# piZero_node.net
KiCad netlist of a schematic drawn in EAGLE
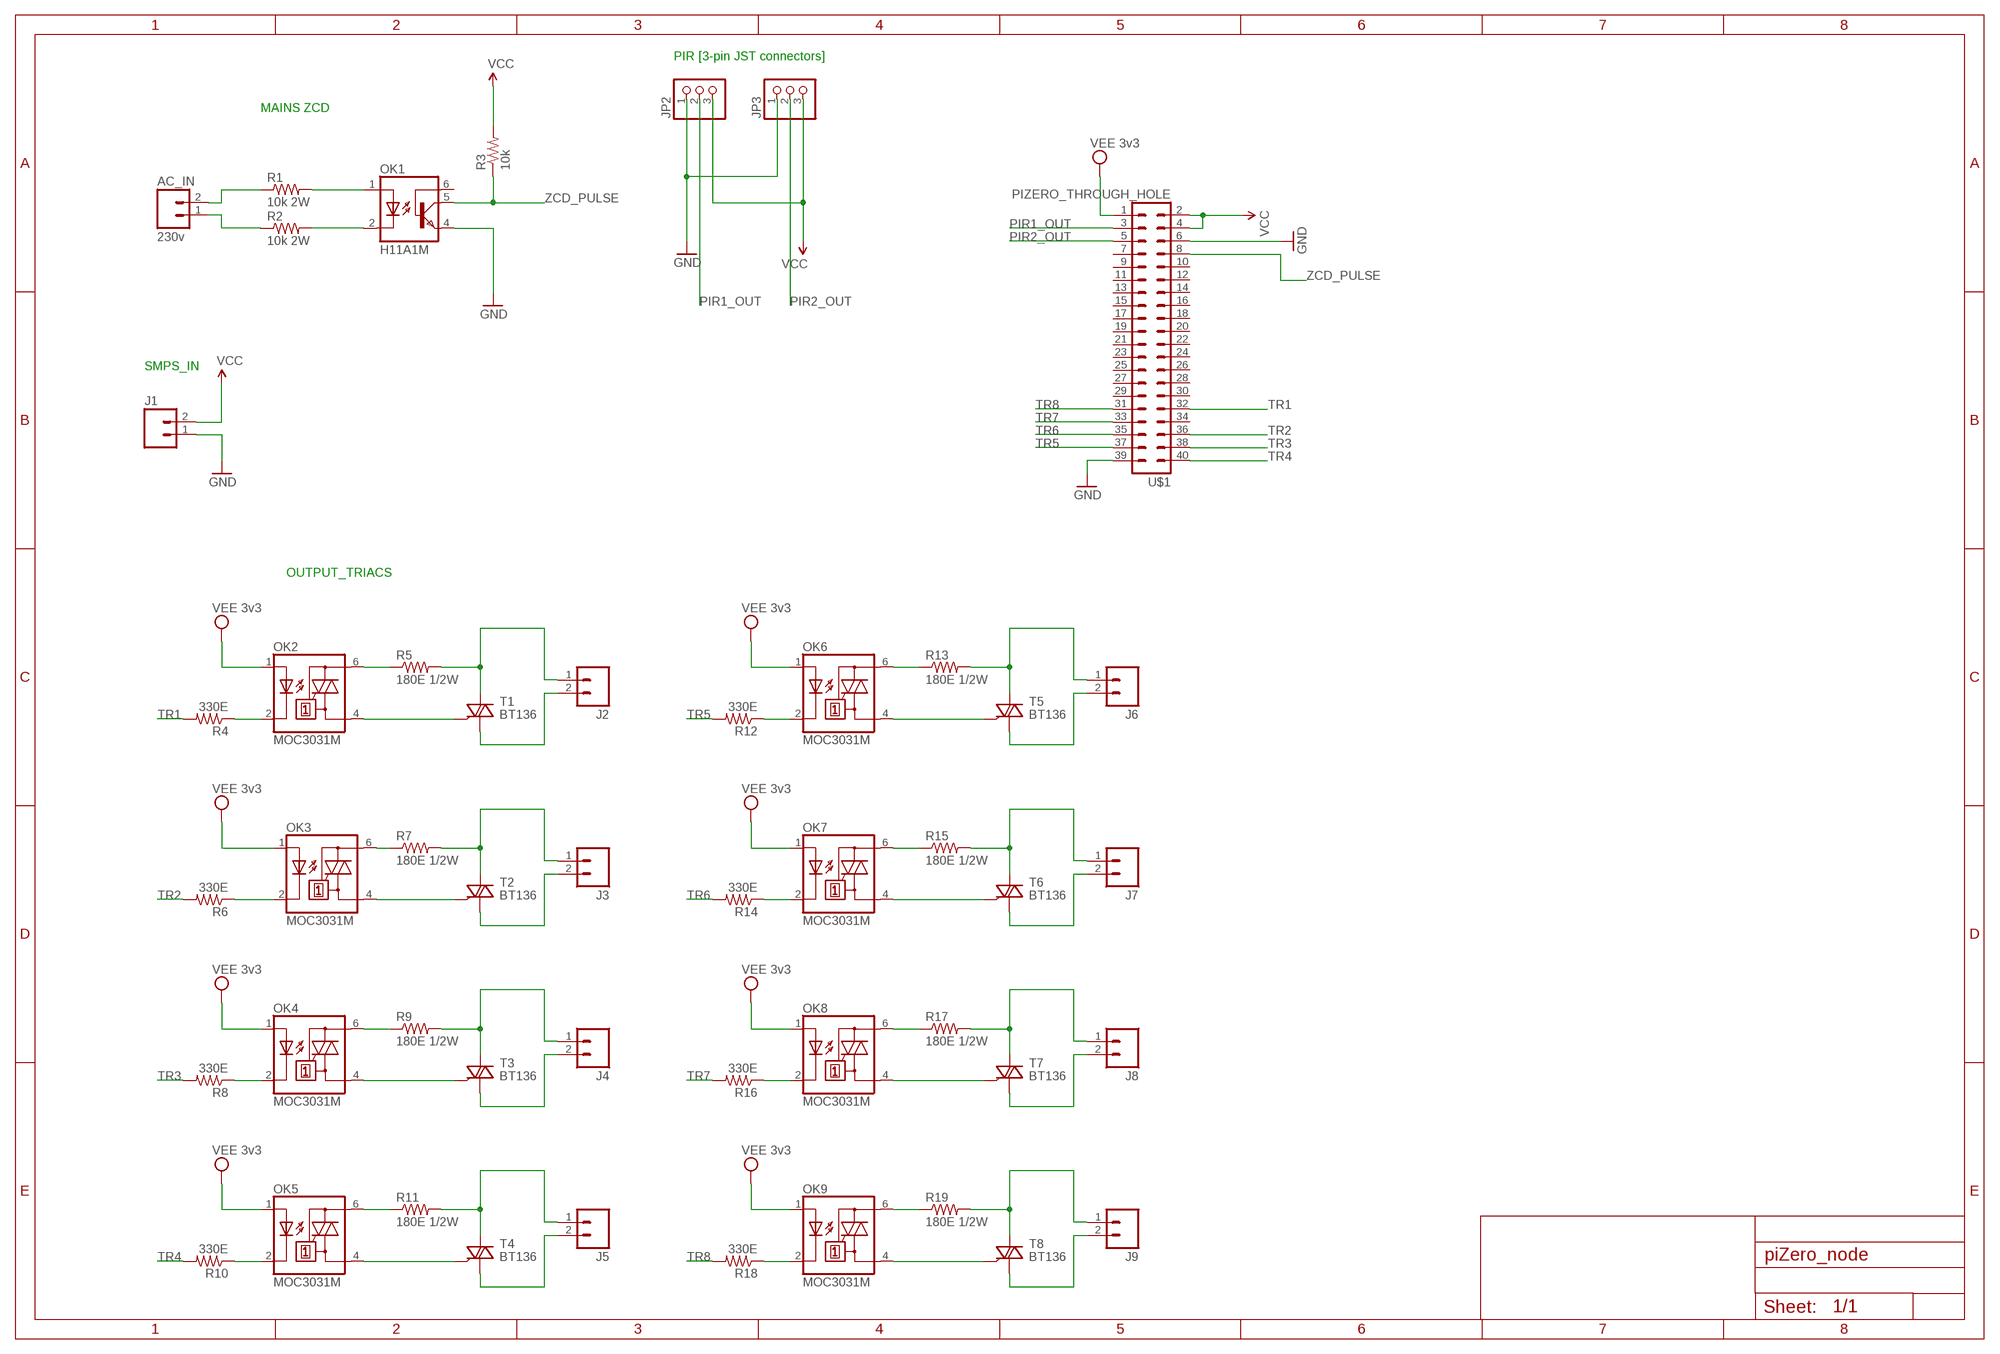
[diagram p0: schematic, sheet 1]

(export (version "E")
  (design (tool "Eeschema 10.0.6"))
  (components
    (comp (ref "AC_IN")
      (value "230v")
      (footprint "eagle-import:SCREWTERMINAL-3.5MM-2_LOCK")
      (libsource (lib "eagle-import") (part "M023.5MM_LOCK"))
    )
    (comp (ref "J1")
      (value "M023.5MM_LOCK")
      (footprint "eagle-import:SCREWTERMINAL-3.5MM-2_LOCK")
      (libsource (lib "eagle-import") (part "M023.5MM_LOCK"))
    )
    (comp (ref "J2")
      (value "M023.5MM_LOCK")
      (footprint "eagle-import:SCREWTERMINAL-3.5MM-2_LOCK")
      (libsource (lib "eagle-import") (part "M023.5MM_LOCK"))
    )
    (comp (ref "J3")
      (value "M023.5MM_LOCK")
      (footprint "eagle-import:SCREWTERMINAL-3.5MM-2_LOCK")
      (libsource (lib "eagle-import") (part "M023.5MM_LOCK"))
    )
    (comp (ref "J4")
      (value "M023.5MM_LOCK")
      (footprint "eagle-import:SCREWTERMINAL-3.5MM-2_LOCK")
      (libsource (lib "eagle-import") (part "M023.5MM_LOCK"))
    )
    (comp (ref "J5")
      (value "M023.5MM_LOCK")
      (footprint "eagle-import:SCREWTERMINAL-3.5MM-2_LOCK")
      (libsource (lib "eagle-import") (part "M023.5MM_LOCK"))
    )
    (comp (ref "J6")
      (value "M023.5MM_LOCK")
      (footprint "eagle-import:SCREWTERMINAL-3.5MM-2_LOCK")
      (libsource (lib "eagle-import") (part "M023.5MM_LOCK"))
    )
    (comp (ref "J7")
      (value "M023.5MM_LOCK")
      (footprint "eagle-import:SCREWTERMINAL-3.5MM-2_LOCK")
      (libsource (lib "eagle-import") (part "M023.5MM_LOCK"))
    )
    (comp (ref "J8")
      (value "M023.5MM_LOCK")
      (footprint "eagle-import:SCREWTERMINAL-3.5MM-2_LOCK")
      (libsource (lib "eagle-import") (part "M023.5MM_LOCK"))
    )
    (comp (ref "J9")
      (value "M023.5MM_LOCK")
      (footprint "eagle-import:SCREWTERMINAL-3.5MM-2_LOCK")
      (libsource (lib "eagle-import") (part "M023.5MM_LOCK"))
    )
    (comp (ref "JP2")
      (value "PINHD-1X3")
      (footprint "eagle-import:1X03")
      (libsource (lib "eagle-import") (part "PINHD-1X3"))
    )
    (comp (ref "JP3")
      (value "PINHD-1X3")
      (footprint "eagle-import:1X03")
      (libsource (lib "eagle-import") (part "PINHD-1X3"))
    )
    (comp (ref "OK1")
      (value "H11A1M")
      (footprint "eagle-import:DIL06")
      (fields (field (name "MPN") "H11A1-M"))
      (libsource (lib "eagle-import") (part "H11A?M1"))
    )
    (comp (ref "OK2")
      (value "MOC3031M")
      (footprint "eagle-import:DIL06")
      (fields (field (name "MF") "FAIRCHILD SEMICONDUCTOR"))
      (libsource (lib "eagle-import") (part "MOC3031M"))
    )
    (comp (ref "OK3")
      (value "MOC3031M")
      (footprint "eagle-import:DIL06")
      (fields (field (name "MF") "FAIRCHILD SEMICONDUCTOR"))
      (libsource (lib "eagle-import") (part "MOC3031M"))
    )
    (comp (ref "OK4")
      (value "MOC3031M")
      (footprint "eagle-import:DIL06")
      (fields (field (name "MF") "FAIRCHILD SEMICONDUCTOR"))
      (libsource (lib "eagle-import") (part "MOC3031M"))
    )
    (comp (ref "OK5")
      (value "MOC3031M")
      (footprint "eagle-import:DIL06")
      (fields (field (name "MF") "FAIRCHILD SEMICONDUCTOR"))
      (libsource (lib "eagle-import") (part "MOC3031M"))
    )
    (comp (ref "OK6")
      (value "MOC3031M")
      (footprint "eagle-import:DIL06")
      (fields (field (name "MF") "FAIRCHILD SEMICONDUCTOR"))
      (libsource (lib "eagle-import") (part "MOC3031M"))
    )
    (comp (ref "OK7")
      (value "MOC3031M")
      (footprint "eagle-import:DIL06")
      (fields (field (name "MF") "FAIRCHILD SEMICONDUCTOR"))
      (libsource (lib "eagle-import") (part "MOC3031M"))
    )
    (comp (ref "OK8")
      (value "MOC3031M")
      (footprint "eagle-import:DIL06")
      (fields (field (name "MF") "FAIRCHILD SEMICONDUCTOR"))
      (libsource (lib "eagle-import") (part "MOC3031M"))
    )
    (comp (ref "OK9")
      (value "MOC3031M")
      (footprint "eagle-import:DIL06")
      (fields (field (name "MF") "FAIRCHILD SEMICONDUCTOR"))
      (libsource (lib "eagle-import") (part "MOC3031M"))
    )
    (comp (ref "R1")
      (value "10k 2W")
      (footprint "eagle-import:AXIAL-0.8")
      (libsource (lib "eagle-import") (part "RESISTORPTH-2W"))
    )
    (comp (ref "R2")
      (value "10k 2W")
      (footprint "eagle-import:AXIAL-0.8")
      (libsource (lib "eagle-import") (part "RESISTORPTH-2W"))
    )
    (comp (ref "R3")
      (value "10k")
      (footprint "eagle-import:AXIAL-0.4")
      (libsource (lib "eagle-import") (part "RESISTORPTH-1/4W"))
    )
    (comp (ref "R4")
      (value "330E")
      (footprint "eagle-import:AXIAL-0.4")
      (libsource (lib "eagle-import") (part "RESISTORPTH-1/4W"))
    )
    (comp (ref "R5")
      (value "180E 1/2W")
      (footprint "eagle-import:AXIAL-0.5")
      (libsource (lib "eagle-import") (part "RESISTORPTH-1/2W"))
    )
    (comp (ref "R6")
      (value "330E")
      (footprint "eagle-import:AXIAL-0.4")
      (libsource (lib "eagle-import") (part "RESISTORPTH-1/4W"))
    )
    (comp (ref "R7")
      (value "180E 1/2W")
      (footprint "eagle-import:AXIAL-0.5")
      (libsource (lib "eagle-import") (part "RESISTORPTH-1/2W"))
    )
    (comp (ref "R8")
      (value "330E")
      (footprint "eagle-import:AXIAL-0.4")
      (libsource (lib "eagle-import") (part "RESISTORPTH-1/4W"))
    )
    (comp (ref "R9")
      (value "180E 1/2W")
      (footprint "eagle-import:AXIAL-0.5")
      (libsource (lib "eagle-import") (part "RESISTORPTH-1/2W"))
    )
    (comp (ref "R10")
      (value "330E")
      (footprint "eagle-import:AXIAL-0.4")
      (libsource (lib "eagle-import") (part "RESISTORPTH-1/4W"))
    )
    (comp (ref "R11")
      (value "180E 1/2W")
      (footprint "eagle-import:AXIAL-0.5")
      (libsource (lib "eagle-import") (part "RESISTORPTH-1/2W"))
    )
    (comp (ref "R12")
      (value "330E")
      (footprint "eagle-import:AXIAL-0.4")
      (libsource (lib "eagle-import") (part "RESISTORPTH-1/4W"))
    )
    (comp (ref "R13")
      (value "180E 1/2W")
      (footprint "eagle-import:AXIAL-0.5")
      (libsource (lib "eagle-import") (part "RESISTORPTH-1/2W"))
    )
    (comp (ref "R14")
      (value "330E")
      (footprint "eagle-import:AXIAL-0.4")
      (libsource (lib "eagle-import") (part "RESISTORPTH-1/4W"))
    )
    (comp (ref "R15")
      (value "180E 1/2W")
      (footprint "eagle-import:AXIAL-0.5")
      (libsource (lib "eagle-import") (part "RESISTORPTH-1/2W"))
    )
    (comp (ref "R16")
      (value "330E")
      (footprint "eagle-import:AXIAL-0.4")
      (libsource (lib "eagle-import") (part "RESISTORPTH-1/4W"))
    )
    (comp (ref "R17")
      (value "180E 1/2W")
      (footprint "eagle-import:AXIAL-0.5")
      (libsource (lib "eagle-import") (part "RESISTORPTH-1/2W"))
    )
    (comp (ref "R18")
      (value "330E")
      (footprint "eagle-import:AXIAL-0.4")
      (libsource (lib "eagle-import") (part "RESISTORPTH-1/4W"))
    )
    (comp (ref "R19")
      (value "180E 1/2W")
      (footprint "eagle-import:AXIAL-0.5")
      (libsource (lib "eagle-import") (part "RESISTORPTH-1/2W"))
    )
    (comp (ref "T1")
      (value "BT136")
      (footprint "eagle-import:TO220AB")
      (libsource (lib "eagle-import") (part "BT136"))
    )
    (comp (ref "T2")
      (value "BT136")
      (footprint "eagle-import:TO220AB")
      (libsource (lib "eagle-import") (part "BT136"))
    )
    (comp (ref "T3")
      (value "BT136")
      (footprint "eagle-import:TO220AB")
      (libsource (lib "eagle-import") (part "BT136"))
    )
    (comp (ref "T4")
      (value "BT136")
      (footprint "eagle-import:TO220AB")
      (libsource (lib "eagle-import") (part "BT136"))
    )
    (comp (ref "T5")
      (value "BT136")
      (footprint "eagle-import:TO220AB")
      (libsource (lib "eagle-import") (part "BT136"))
    )
    (comp (ref "T6")
      (value "BT136")
      (footprint "eagle-import:TO220AB")
      (libsource (lib "eagle-import") (part "BT136"))
    )
    (comp (ref "T7")
      (value "BT136")
      (footprint "eagle-import:TO220AB")
      (libsource (lib "eagle-import") (part "BT136"))
    )
    (comp (ref "T8")
      (value "BT136")
      (footprint "eagle-import:TO220AB")
      (libsource (lib "eagle-import") (part "BT136"))
    )
    (comp (ref "U$1")
      (value "PIZERO_THROUGH_HOLE")
      (footprint "eagle-import:PIZERO_THOUGH_HOLE")
      (libsource (lib "eagle-import") (part "PIZERO_THROUGH_HOLE"))
    )
  )
  (nets
    (net (code "1") (name "/PIR1_OUT") (class "Default")
      (node (ref "JP2") (pin "2") (pinfunction "2_2") (pintype "passive"))
      (node (ref "U$1") (pin "3") (pinfunction "3_3") (pintype "passive"))
    )
    (net (code "2") (name "/PIR2_OUT") (class "Default")
      (node (ref "JP3") (pin "2") (pinfunction "2_2") (pintype "passive"))
      (node (ref "U$1") (pin "5") (pinfunction "5_5") (pintype "passive"))
    )
    (net (code "3") (name "/TR1") (class "Default")
      (node (ref "R4") (pin "P$2") (pinfunction "2_P$2") (pintype "passive"))
      (node (ref "U$1") (pin "32") (pinfunction "32_32") (pintype "passive"))
    )
    (net (code "4") (name "/TR2") (class "Default")
      (node (ref "R6") (pin "P$2") (pinfunction "2_P$2") (pintype "passive"))
      (node (ref "U$1") (pin "36") (pinfunction "36_36") (pintype "passive"))
    )
    (net (code "5") (name "/TR3") (class "Default")
      (node (ref "R8") (pin "P$2") (pinfunction "2_P$2") (pintype "passive"))
      (node (ref "U$1") (pin "38") (pinfunction "38_38") (pintype "passive"))
    )
    (net (code "6") (name "/TR4") (class "Default")
      (node (ref "R10") (pin "P$2") (pinfunction "2_P$2") (pintype "passive"))
      (node (ref "U$1") (pin "40") (pinfunction "40_40") (pintype "passive"))
    )
    (net (code "7") (name "/TR5") (class "Default")
      (node (ref "R12") (pin "P$2") (pinfunction "2_P$2") (pintype "passive"))
      (node (ref "U$1") (pin "37") (pinfunction "37_37") (pintype "passive"))
    )
    (net (code "8") (name "/TR6") (class "Default")
      (node (ref "R14") (pin "P$2") (pinfunction "2_P$2") (pintype "passive"))
      (node (ref "U$1") (pin "35") (pinfunction "35_35") (pintype "passive"))
    )
    (net (code "9") (name "/TR7") (class "Default")
      (node (ref "R16") (pin "P$2") (pinfunction "2_P$2") (pintype "passive"))
      (node (ref "U$1") (pin "33") (pinfunction "33_33") (pintype "passive"))
    )
    (net (code "10") (name "/TR8") (class "Default")
      (node (ref "R18") (pin "P$2") (pinfunction "2_P$2") (pintype "passive"))
      (node (ref "U$1") (pin "31") (pinfunction "31_31") (pintype "passive"))
    )
    (net (code "11") (name "/ZCD_PULSE") (class "Default")
      (node (ref "OK1") (pin "5") (pinfunction "COL_5") (pintype "passive"))
      (node (ref "R3") (pin "P$1") (pinfunction "1_P$1") (pintype "passive"))
      (node (ref "U$1") (pin "8") (pinfunction "8_8") (pintype "passive"))
    )
    (net (code "12") (name "GND") (class "Default")
      (node (ref "J1") (pin "1") (pinfunction "1_1") (pintype "passive"))
      (node (ref "JP2") (pin "1") (pinfunction "1_1") (pintype "passive"))
      (node (ref "JP3") (pin "1") (pinfunction "1_1") (pintype "passive"))
      (node (ref "OK1") (pin "4") (pinfunction "EMI_4") (pintype "passive"))
      (node (ref "U$1") (pin "39") (pinfunction "39_39") (pintype "passive"))
      (node (ref "U$1") (pin "6") (pinfunction "6_6") (pintype "passive"))
    )
    (net (code "13") (name "Net-(OK1-A)") (class "Default")
      (node (ref "OK1") (pin "1") (pinfunction "A_1") (pintype "passive"))
      (node (ref "R1") (pin "P$2") (pinfunction "2_P$2") (pintype "passive"))
    )
    (net (code "14") (name "Net-(OK1-C)") (class "Default")
      (node (ref "OK1") (pin "2") (pinfunction "C_2") (pintype "passive"))
      (node (ref "R2") (pin "P$2") (pinfunction "2_P$2") (pintype "passive"))
    )
    (net (code "15") (name "Net-(OK2-A1)") (class "Default")
      (node (ref "OK2") (pin "4") (pinfunction "A1_4") (pintype "passive"))
      (node (ref "T1") (pin "3") (pinfunction "G_3") (pintype "passive"))
    )
    (net (code "16") (name "Net-(OK2-A2)") (class "Default")
      (node (ref "OK2") (pin "6") (pinfunction "A2_6") (pintype "passive"))
      (node (ref "R5") (pin "P$1") (pinfunction "1_P$1") (pintype "passive"))
    )
    (net (code "17") (name "Net-(OK2-C)") (class "Default")
      (node (ref "OK2") (pin "2") (pinfunction "C_2") (pintype "passive"))
      (node (ref "R4") (pin "P$1") (pinfunction "1_P$1") (pintype "passive"))
    )
    (net (code "18") (name "Net-(OK3-A1)") (class "Default")
      (node (ref "OK3") (pin "4") (pinfunction "A1_4") (pintype "passive"))
      (node (ref "T2") (pin "3") (pinfunction "G_3") (pintype "passive"))
    )
    (net (code "19") (name "Net-(OK3-A2)") (class "Default")
      (node (ref "OK3") (pin "6") (pinfunction "A2_6") (pintype "passive"))
      (node (ref "R7") (pin "P$1") (pinfunction "1_P$1") (pintype "passive"))
    )
    (net (code "20") (name "Net-(OK3-C)") (class "Default")
      (node (ref "OK3") (pin "2") (pinfunction "C_2") (pintype "passive"))
      (node (ref "R6") (pin "P$1") (pinfunction "1_P$1") (pintype "passive"))
    )
    (net (code "21") (name "Net-(OK4-A1)") (class "Default")
      (node (ref "OK4") (pin "4") (pinfunction "A1_4") (pintype "passive"))
      (node (ref "T3") (pin "3") (pinfunction "G_3") (pintype "passive"))
    )
    (net (code "22") (name "Net-(OK4-A2)") (class "Default")
      (node (ref "OK4") (pin "6") (pinfunction "A2_6") (pintype "passive"))
      (node (ref "R9") (pin "P$1") (pinfunction "1_P$1") (pintype "passive"))
    )
    (net (code "23") (name "Net-(OK4-C)") (class "Default")
      (node (ref "OK4") (pin "2") (pinfunction "C_2") (pintype "passive"))
      (node (ref "R8") (pin "P$1") (pinfunction "1_P$1") (pintype "passive"))
    )
    (net (code "24") (name "Net-(OK5-A1)") (class "Default")
      (node (ref "OK5") (pin "4") (pinfunction "A1_4") (pintype "passive"))
      (node (ref "T4") (pin "3") (pinfunction "G_3") (pintype "passive"))
    )
    (net (code "25") (name "Net-(OK5-A2)") (class "Default")
      (node (ref "OK5") (pin "6") (pinfunction "A2_6") (pintype "passive"))
      (node (ref "R11") (pin "P$1") (pinfunction "1_P$1") (pintype "passive"))
    )
    (net (code "26") (name "Net-(OK5-C)") (class "Default")
      (node (ref "OK5") (pin "2") (pinfunction "C_2") (pintype "passive"))
      (node (ref "R10") (pin "P$1") (pinfunction "1_P$1") (pintype "passive"))
    )
    (net (code "27") (name "Net-(OK6-A1)") (class "Default")
      (node (ref "OK6") (pin "4") (pinfunction "A1_4") (pintype "passive"))
      (node (ref "T5") (pin "3") (pinfunction "G_3") (pintype "passive"))
    )
    (net (code "28") (name "Net-(OK6-A2)") (class "Default")
      (node (ref "OK6") (pin "6") (pinfunction "A2_6") (pintype "passive"))
      (node (ref "R13") (pin "P$1") (pinfunction "1_P$1") (pintype "passive"))
    )
    (net (code "29") (name "Net-(OK6-C)") (class "Default")
      (node (ref "OK6") (pin "2") (pinfunction "C_2") (pintype "passive"))
      (node (ref "R12") (pin "P$1") (pinfunction "1_P$1") (pintype "passive"))
    )
    (net (code "30") (name "Net-(OK7-A1)") (class "Default")
      (node (ref "OK7") (pin "4") (pinfunction "A1_4") (pintype "passive"))
      (node (ref "T6") (pin "3") (pinfunction "G_3") (pintype "passive"))
    )
    (net (code "31") (name "Net-(OK7-A2)") (class "Default")
      (node (ref "OK7") (pin "6") (pinfunction "A2_6") (pintype "passive"))
      (node (ref "R15") (pin "P$1") (pinfunction "1_P$1") (pintype "passive"))
    )
    (net (code "32") (name "Net-(OK7-C)") (class "Default")
      (node (ref "OK7") (pin "2") (pinfunction "C_2") (pintype "passive"))
      (node (ref "R14") (pin "P$1") (pinfunction "1_P$1") (pintype "passive"))
    )
    (net (code "33") (name "Net-(OK8-A1)") (class "Default")
      (node (ref "OK8") (pin "4") (pinfunction "A1_4") (pintype "passive"))
      (node (ref "T7") (pin "3") (pinfunction "G_3") (pintype "passive"))
    )
    (net (code "34") (name "Net-(OK8-A2)") (class "Default")
      (node (ref "OK8") (pin "6") (pinfunction "A2_6") (pintype "passive"))
      (node (ref "R17") (pin "P$1") (pinfunction "1_P$1") (pintype "passive"))
    )
    (net (code "35") (name "Net-(OK8-C)") (class "Default")
      (node (ref "OK8") (pin "2") (pinfunction "C_2") (pintype "passive"))
      (node (ref "R16") (pin "P$1") (pinfunction "1_P$1") (pintype "passive"))
    )
    (net (code "36") (name "Net-(OK9-A1)") (class "Default")
      (node (ref "OK9") (pin "4") (pinfunction "A1_4") (pintype "passive"))
      (node (ref "T8") (pin "3") (pinfunction "G_3") (pintype "passive"))
    )
    (net (code "37") (name "Net-(OK9-A2)") (class "Default")
      (node (ref "OK9") (pin "6") (pinfunction "A2_6") (pintype "passive"))
      (node (ref "R19") (pin "P$1") (pinfunction "1_P$1") (pintype "passive"))
    )
    (net (code "38") (name "Net-(OK9-C)") (class "Default")
      (node (ref "OK9") (pin "2") (pinfunction "C_2") (pintype "passive"))
      (node (ref "R18") (pin "P$1") (pinfunction "1_P$1") (pintype "passive"))
    )
    (net (code "39") (name "Net-(R1-1)") (class "Default")
      (node (ref "AC_IN") (pin "2") (pinfunction "2_2") (pintype "passive"))
      (node (ref "R1") (pin "P$1") (pinfunction "1_P$1") (pintype "passive"))
    )
    (net (code "40") (name "Net-(R2-1)") (class "Default")
      (node (ref "AC_IN") (pin "1") (pinfunction "1_1") (pintype "passive"))
      (node (ref "R2") (pin "P$1") (pinfunction "1_P$1") (pintype "passive"))
    )
    (net (code "41") (name "Net-(R5-2)") (class "Default")
      (node (ref "J2") (pin "1") (pinfunction "1_1") (pintype "passive"))
      (node (ref "R5") (pin "P$2") (pinfunction "2_P$2") (pintype "passive"))
      (node (ref "T1") (pin "2") (pinfunction "A2_2") (pintype "passive"))
    )
    (net (code "42") (name "Net-(R7-2)") (class "Default")
      (node (ref "J3") (pin "1") (pinfunction "1_1") (pintype "passive"))
      (node (ref "R7") (pin "P$2") (pinfunction "2_P$2") (pintype "passive"))
      (node (ref "T2") (pin "2") (pinfunction "A2_2") (pintype "passive"))
    )
    (net (code "43") (name "Net-(R9-2)") (class "Default")
      (node (ref "J4") (pin "1") (pinfunction "1_1") (pintype "passive"))
      (node (ref "R9") (pin "P$2") (pinfunction "2_P$2") (pintype "passive"))
      (node (ref "T3") (pin "2") (pinfunction "A2_2") (pintype "passive"))
    )
    (net (code "44") (name "Net-(R11-2)") (class "Default")
      (node (ref "J5") (pin "1") (pinfunction "1_1") (pintype "passive"))
      (node (ref "R11") (pin "P$2") (pinfunction "2_P$2") (pintype "passive"))
      (node (ref "T4") (pin "2") (pinfunction "A2_2") (pintype "passive"))
    )
    (net (code "45") (name "Net-(R13-2)") (class "Default")
      (node (ref "J6") (pin "1") (pinfunction "1_1") (pintype "passive"))
      (node (ref "R13") (pin "P$2") (pinfunction "2_P$2") (pintype "passive"))
      (node (ref "T5") (pin "2") (pinfunction "A2_2") (pintype "passive"))
    )
    (net (code "46") (name "Net-(R15-2)") (class "Default")
      (node (ref "J7") (pin "1") (pinfunction "1_1") (pintype "passive"))
      (node (ref "R15") (pin "P$2") (pinfunction "2_P$2") (pintype "passive"))
      (node (ref "T6") (pin "2") (pinfunction "A2_2") (pintype "passive"))
    )
    (net (code "47") (name "Net-(R17-2)") (class "Default")
      (node (ref "J8") (pin "1") (pinfunction "1_1") (pintype "passive"))
      (node (ref "R17") (pin "P$2") (pinfunction "2_P$2") (pintype "passive"))
      (node (ref "T7") (pin "2") (pinfunction "A2_2") (pintype "passive"))
    )
    (net (code "48") (name "Net-(R19-2)") (class "Default")
      (node (ref "J9") (pin "1") (pinfunction "1_1") (pintype "passive"))
      (node (ref "R19") (pin "P$2") (pinfunction "2_P$2") (pintype "passive"))
      (node (ref "T8") (pin "2") (pinfunction "A2_2") (pintype "passive"))
    )
    (net (code "49") (name "Net-(T1-A1)") (class "Default")
      (node (ref "J2") (pin "2") (pinfunction "2_2") (pintype "passive"))
      (node (ref "T1") (pin "1") (pinfunction "A1_1") (pintype "passive"))
    )
    (net (code "50") (name "Net-(T2-A1)") (class "Default")
      (node (ref "J3") (pin "2") (pinfunction "2_2") (pintype "passive"))
      (node (ref "T2") (pin "1") (pinfunction "A1_1") (pintype "passive"))
    )
    (net (code "51") (name "Net-(T3-A1)") (class "Default")
      (node (ref "J4") (pin "2") (pinfunction "2_2") (pintype "passive"))
      (node (ref "T3") (pin "1") (pinfunction "A1_1") (pintype "passive"))
    )
    (net (code "52") (name "Net-(T4-A1)") (class "Default")
      (node (ref "J5") (pin "2") (pinfunction "2_2") (pintype "passive"))
      (node (ref "T4") (pin "1") (pinfunction "A1_1") (pintype "passive"))
    )
    (net (code "53") (name "Net-(T5-A1)") (class "Default")
      (node (ref "J6") (pin "2") (pinfunction "2_2") (pintype "passive"))
      (node (ref "T5") (pin "1") (pinfunction "A1_1") (pintype "passive"))
    )
    (net (code "54") (name "Net-(T6-A1)") (class "Default")
      (node (ref "J7") (pin "2") (pinfunction "2_2") (pintype "passive"))
      (node (ref "T6") (pin "1") (pinfunction "A1_1") (pintype "passive"))
    )
    (net (code "55") (name "Net-(T7-A1)") (class "Default")
      (node (ref "J8") (pin "2") (pinfunction "2_2") (pintype "passive"))
      (node (ref "T7") (pin "1") (pinfunction "A1_1") (pintype "passive"))
    )
    (net (code "56") (name "Net-(T8-A1)") (class "Default")
      (node (ref "J9") (pin "2") (pinfunction "2_2") (pintype "passive"))
      (node (ref "T8") (pin "1") (pinfunction "A1_1") (pintype "passive"))
    )
    (net (code "57") (name "VCC") (class "Default")
      (node (ref "J1") (pin "2") (pinfunction "2_2") (pintype "passive"))
      (node (ref "JP2") (pin "3") (pinfunction "3_3") (pintype "passive"))
      (node (ref "JP3") (pin "3") (pinfunction "3_3") (pintype "passive"))
      (node (ref "R3") (pin "P$2") (pinfunction "2_P$2") (pintype "passive"))
      (node (ref "U$1") (pin "2") (pinfunction "2_2") (pintype "passive"))
      (node (ref "U$1") (pin "4") (pinfunction "4_4") (pintype "passive"))
    )
    (net (code "58") (name "VEE 3v3") (class "Default")
      (node (ref "OK2") (pin "1") (pinfunction "A_1") (pintype "passive"))
      (node (ref "OK3") (pin "1") (pinfunction "A_1") (pintype "passive"))
      (node (ref "OK4") (pin "1") (pinfunction "A_1") (pintype "passive"))
      (node (ref "OK5") (pin "1") (pinfunction "A_1") (pintype "passive"))
      (node (ref "OK6") (pin "1") (pinfunction "A_1") (pintype "passive"))
      (node (ref "OK7") (pin "1") (pinfunction "A_1") (pintype "passive"))
      (node (ref "OK8") (pin "1") (pinfunction "A_1") (pintype "passive"))
      (node (ref "OK9") (pin "1") (pinfunction "A_1") (pintype "passive"))
      (node (ref "U$1") (pin "1") (pinfunction "1_1") (pintype "passive"))
    )
    (net (code "59") (name "unconnected-(OK1-BAS-Pad6)") (class "Default")
      (node (ref "OK1") (pin "6") (pinfunction "BAS_6") (pintype "passive"))
    )
    (net (code "60") (name "unconnected-(U$1-Pad7)") (class "Default")
      (node (ref "U$1") (pin "7") (pinfunction "7_7") (pintype "passive"))
    )
    (net (code "61") (name "unconnected-(U$1-Pad9)") (class "Default")
      (node (ref "U$1") (pin "9") (pinfunction "9_9") (pintype "passive"))
    )
    (net (code "62") (name "unconnected-(U$1-Pad10)") (class "Default")
      (node (ref "U$1") (pin "10") (pinfunction "10_10") (pintype "passive"))
    )
    (net (code "63") (name "unconnected-(U$1-Pad11)") (class "Default")
      (node (ref "U$1") (pin "11") (pinfunction "11_11") (pintype "passive"))
    )
    (net (code "64") (name "unconnected-(U$1-Pad12)") (class "Default")
      (node (ref "U$1") (pin "12") (pinfunction "12_12") (pintype "passive"))
    )
    (net (code "65") (name "unconnected-(U$1-Pad13)") (class "Default")
      (node (ref "U$1") (pin "13") (pinfunction "13_13") (pintype "passive"))
    )
    (net (code "66") (name "unconnected-(U$1-Pad14)") (class "Default")
      (node (ref "U$1") (pin "14") (pinfunction "14_14") (pintype "passive"))
    )
    (net (code "67") (name "unconnected-(U$1-Pad15)") (class "Default")
      (node (ref "U$1") (pin "15") (pinfunction "15_15") (pintype "passive"))
    )
    (net (code "68") (name "unconnected-(U$1-Pad16)") (class "Default")
      (node (ref "U$1") (pin "16") (pinfunction "16_16") (pintype "passive"))
    )
    (net (code "69") (name "unconnected-(U$1-Pad17)") (class "Default")
      (node (ref "U$1") (pin "17") (pinfunction "17_17") (pintype "passive"))
    )
    (net (code "70") (name "unconnected-(U$1-Pad18)") (class "Default")
      (node (ref "U$1") (pin "18") (pinfunction "18_18") (pintype "passive"))
    )
    (net (code "71") (name "unconnected-(U$1-Pad19)") (class "Default")
      (node (ref "U$1") (pin "19") (pinfunction "19_19") (pintype "passive"))
    )
    (net (code "72") (name "unconnected-(U$1-Pad20)") (class "Default")
      (node (ref "U$1") (pin "20") (pinfunction "20_20") (pintype "passive"))
    )
    (net (code "73") (name "unconnected-(U$1-Pad21)") (class "Default")
      (node (ref "U$1") (pin "21") (pinfunction "21_21") (pintype "passive"))
    )
    (net (code "74") (name "unconnected-(U$1-Pad22)") (class "Default")
      (node (ref "U$1") (pin "22") (pinfunction "22_22") (pintype "passive"))
    )
    (net (code "75") (name "unconnected-(U$1-Pad23)") (class "Default")
      (node (ref "U$1") (pin "23") (pinfunction "23_23") (pintype "passive"))
    )
    (net (code "76") (name "unconnected-(U$1-Pad24)") (class "Default")
      (node (ref "U$1") (pin "24") (pinfunction "24_24") (pintype "passive"))
    )
    (net (code "77") (name "unconnected-(U$1-Pad25)") (class "Default")
      (node (ref "U$1") (pin "25") (pinfunction "25_25") (pintype "passive"))
    )
    (net (code "78") (name "unconnected-(U$1-Pad26)") (class "Default")
      (node (ref "U$1") (pin "26") (pinfunction "26_26") (pintype "passive"))
    )
    (net (code "79") (name "unconnected-(U$1-Pad27)") (class "Default")
      (node (ref "U$1") (pin "27") (pinfunction "27_27") (pintype "passive"))
    )
    (net (code "80") (name "unconnected-(U$1-Pad28)") (class "Default")
      (node (ref "U$1") (pin "28") (pinfunction "28_28") (pintype "passive"))
    )
    (net (code "81") (name "unconnected-(U$1-Pad29)") (class "Default")
      (node (ref "U$1") (pin "29") (pinfunction "29_29") (pintype "passive"))
    )
    (net (code "82") (name "unconnected-(U$1-Pad30)") (class "Default")
      (node (ref "U$1") (pin "30") (pinfunction "30_30") (pintype "passive"))
    )
    (net (code "83") (name "unconnected-(U$1-Pad34)") (class "Default")
      (node (ref "U$1") (pin "34") (pinfunction "34_34") (pintype "passive"))
    )
  )
)
